# Chua.net
KiCad netlist of a schematic drawn in Altium Designer
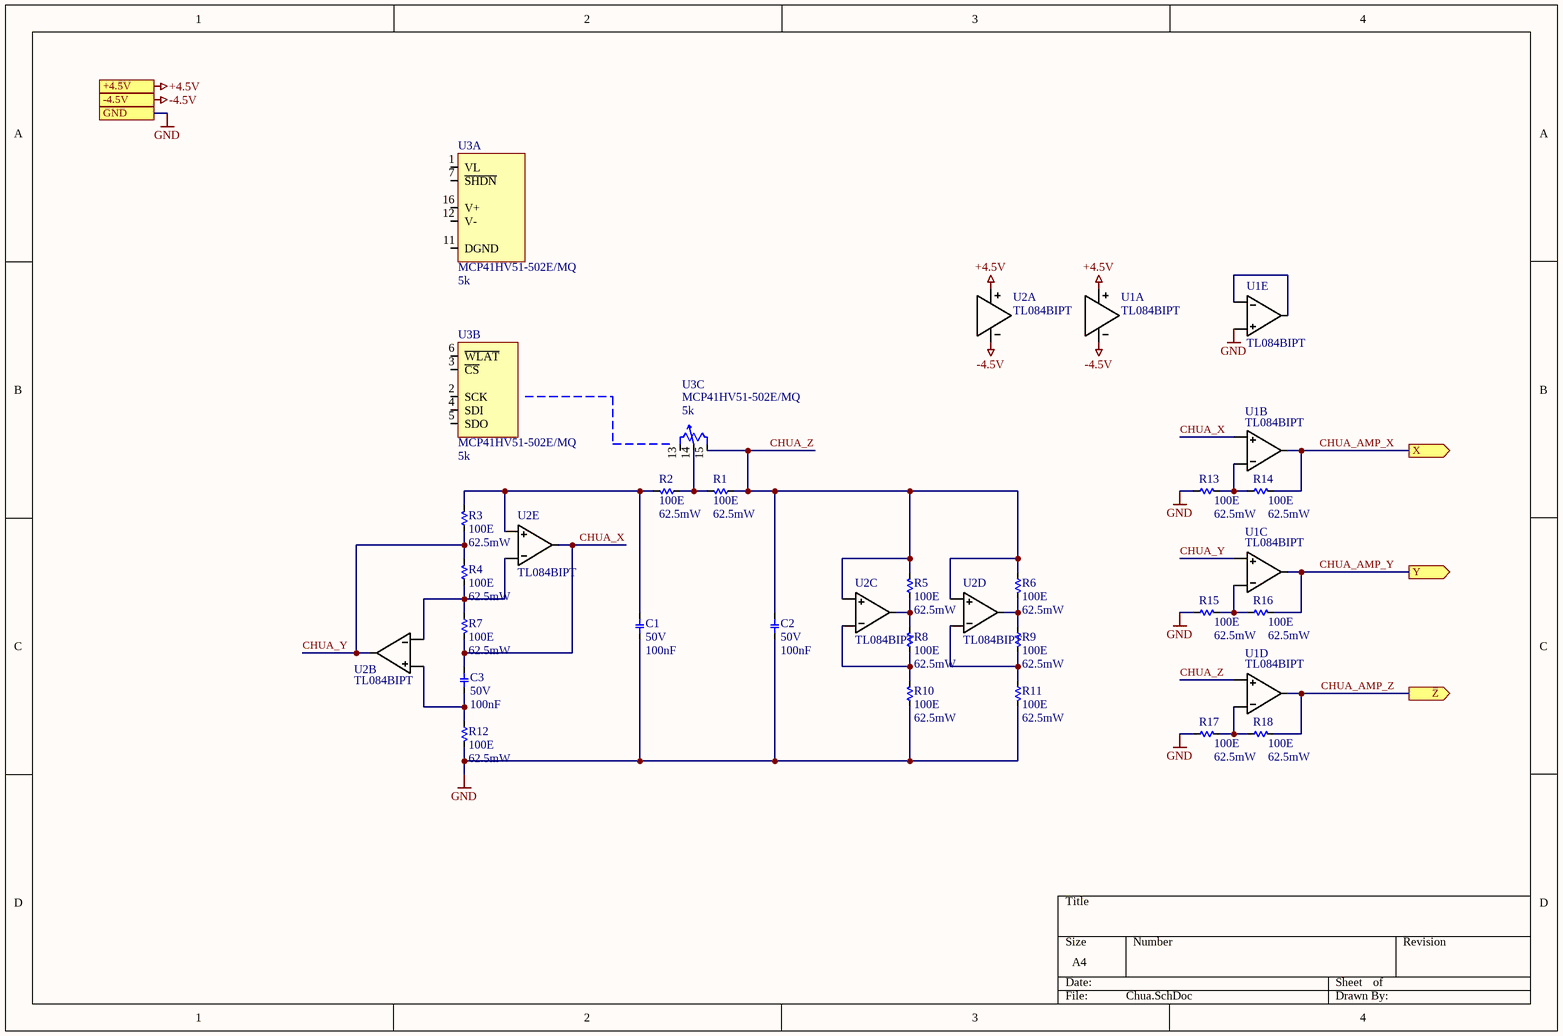
[diagram p0: Chua.SchDoc]

(export (version "E")
  (design (tool "Eeschema 10.0.6"))
  (components
    (comp (ref "C1")
      (value "100nF")
      (footprint "CX7R0402C")
      (description "SMD Capacitor")
      (fields (field (name "VALUE2") "50V") (field (name "Comment") "04025C104JAT2A"))
      (libsource (lib "ChaoticCircuits") (part "kyocera-C-X7R-0402"))
    )
    (comp (ref "C2")
      (value "100nF")
      (footprint "CX7R0402C")
      (description "SMD Capacitor")
      (fields (field (name "VALUE2") "50V") (field (name "Comment") "04025C104JAT2A"))
      (libsource (lib "ChaoticCircuits") (part "kyocera-C-X7R-0402"))
    )
    (comp (ref "C3")
      (value "100nF")
      (footprint "CX7R0402C")
      (description "SMD Capacitor")
      (fields (field (name "VALUE2") "50V") (field (name "Comment") "04025C104JAT2A"))
      (libsource (lib "ChaoticCircuits") (part "kyocera-C-X7R-0402"))
    )
    (comp (ref "R1")
      (value "100E")
      (footprint "RC0402")
      (description "SMD Resistor")
      (fields (field (name "VALUE2") "62.5mW") (field (name "Comment") "0402FR-07100RL"))
      (libsource (lib "ChaoticCircuits") (part "YAGEO-RC-0402"))
    )
    (comp (ref "R2")
      (value "100E")
      (footprint "RC0402")
      (description "SMD Resistor")
      (fields (field (name "VALUE2") "62.5mW") (field (name "Comment") "0402FR-07100RL"))
      (libsource (lib "ChaoticCircuits") (part "YAGEO-RC-0402"))
    )
    (comp (ref "R3")
      (value "100E")
      (footprint "RC0402")
      (description "SMD Resistor")
      (fields (field (name "VALUE2") "62.5mW") (field (name "Comment") "0402FR-07100RL"))
      (libsource (lib "ChaoticCircuits") (part "YAGEO-RC-0402"))
    )
    (comp (ref "R4")
      (value "100E")
      (footprint "RC0402")
      (description "SMD Resistor")
      (fields (field (name "VALUE2") "62.5mW") (field (name "Comment") "0402FR-07100RL"))
      (libsource (lib "ChaoticCircuits") (part "YAGEO-RC-0402"))
    )
    (comp (ref "R5")
      (value "100E")
      (footprint "RC0402")
      (description "SMD Resistor")
      (fields (field (name "VALUE2") "62.5mW") (field (name "Comment") "0402FR-07100RL"))
      (libsource (lib "ChaoticCircuits") (part "YAGEO-RC-0402"))
    )
    (comp (ref "R6")
      (value "100E")
      (footprint "RC0402")
      (description "SMD Resistor")
      (fields (field (name "VALUE2") "62.5mW") (field (name "Comment") "0402FR-07100RL"))
      (libsource (lib "ChaoticCircuits") (part "YAGEO-RC-0402"))
    )
    (comp (ref "R7")
      (value "100E")
      (footprint "RC0402")
      (description "SMD Resistor")
      (fields (field (name "VALUE2") "62.5mW") (field (name "Comment") "0402FR-07100RL"))
      (libsource (lib "ChaoticCircuits") (part "YAGEO-RC-0402"))
    )
    (comp (ref "R8")
      (value "100E")
      (footprint "RC0402")
      (description "SMD Resistor")
      (fields (field (name "VALUE2") "62.5mW") (field (name "Comment") "0402FR-07100RL"))
      (libsource (lib "ChaoticCircuits") (part "YAGEO-RC-0402"))
    )
    (comp (ref "R9")
      (value "100E")
      (footprint "RC0402")
      (description "SMD Resistor")
      (fields (field (name "VALUE2") "62.5mW") (field (name "Comment") "0402FR-07100RL"))
      (libsource (lib "ChaoticCircuits") (part "YAGEO-RC-0402"))
    )
    (comp (ref "R10")
      (value "100E")
      (footprint "RC0402")
      (description "SMD Resistor")
      (fields (field (name "VALUE2") "62.5mW") (field (name "Comment") "0402FR-07100RL"))
      (libsource (lib "ChaoticCircuits") (part "YAGEO-RC-0402"))
    )
    (comp (ref "R11")
      (value "100E")
      (footprint "RC0402")
      (description "SMD Resistor")
      (fields (field (name "VALUE2") "62.5mW") (field (name "Comment") "0402FR-07100RL"))
      (libsource (lib "ChaoticCircuits") (part "YAGEO-RC-0402"))
    )
    (comp (ref "R12")
      (value "100E")
      (footprint "RC0402")
      (description "SMD Resistor")
      (fields (field (name "VALUE2") "62.5mW") (field (name "Comment") "0402FR-07100RL"))
      (libsource (lib "ChaoticCircuits") (part "YAGEO-RC-0402"))
    )
    (comp (ref "R13")
      (value "100E")
      (footprint "RC0402")
      (description "SMD Resistor")
      (fields (field (name "VALUE2") "62.5mW") (field (name "Comment") "0402FR-07100RL"))
      (libsource (lib "ChaoticCircuits") (part "YAGEO-RC-0402"))
    )
    (comp (ref "R14")
      (value "100E")
      (footprint "RC0402")
      (description "SMD Resistor")
      (fields (field (name "VALUE2") "62.5mW") (field (name "Comment") "0402FR-07100RL"))
      (libsource (lib "ChaoticCircuits") (part "YAGEO-RC-0402"))
    )
    (comp (ref "R15")
      (value "100E")
      (footprint "RC0402")
      (description "SMD Resistor")
      (fields (field (name "VALUE2") "62.5mW") (field (name "Comment") "0402FR-07100RL"))
      (libsource (lib "ChaoticCircuits") (part "YAGEO-RC-0402"))
    )
    (comp (ref "R16")
      (value "100E")
      (footprint "RC0402")
      (description "SMD Resistor")
      (fields (field (name "VALUE2") "62.5mW") (field (name "Comment") "0402FR-07100RL"))
      (libsource (lib "ChaoticCircuits") (part "YAGEO-RC-0402"))
    )
    (comp (ref "R17")
      (value "100E")
      (footprint "RC0402")
      (description "SMD Resistor")
      (fields (field (name "VALUE2") "62.5mW") (field (name "Comment") "0402FR-07100RL"))
      (libsource (lib "ChaoticCircuits") (part "YAGEO-RC-0402"))
    )
    (comp (ref "R18")
      (value "100E")
      (footprint "RC0402")
      (description "SMD Resistor")
      (fields (field (name "VALUE2") "62.5mW") (field (name "Comment") "0402FR-07100RL"))
      (libsource (lib "ChaoticCircuits") (part "YAGEO-RC-0402"))
    )
    (comp (ref "U1")
      (value "TL084BIPT")
      (footprint "TSSOP14_0.65_C")
      (description "J-FET Amplifier 4 Circuit - 14-TSSOP")
      (libsource (lib "ChaoticCircuits") (part "TL084"))
    )
    (comp (ref "U2")
      (value "TL084BIPT")
      (footprint "TSSOP14_0.65_C")
      (description "J-FET Amplifier 4 Circuit - 14-TSSOP")
      (libsource (lib "ChaoticCircuits") (part "TL084"))
    )
    (comp (ref "U3")
      (value "MCP41HV51-502E/MQ")
      (footprint "QFN20_0.65_C")
      (description "Digital Potentiometer 5k Ohm 1 Circuit 256 Taps SPI Interface 20-VQFN (5x5)")
      (fields (field (name "ALTIUM_VALUE") "5k"))
      (libsource (lib "ChaoticCircuits") (part "MCP41HV51-502E/MQ"))
    )
  )
  (nets
    (net (code "1") (name "+4.5V") (class "Default")
      (node (ref "U1") (pin "4") (pinfunction "VCC+_4") (pintype "passive"))
      (node (ref "U2") (pin "4") (pinfunction "VCC+_4") (pintype "passive"))
    )
    (net (code "2") (name "-4.5V") (class "Default")
      (node (ref "U1") (pin "11") (pinfunction "VCC-_11") (pintype "passive"))
      (node (ref "U2") (pin "11") (pinfunction "VCC-_11") (pintype "passive"))
    )
    (net (code "3") (name "/CHUA_AMP_X") (class "Default")
      (node (ref "R14") (pin "1") (pinfunction "1_1") (pintype "passive"))
      (node (ref "U1") (pin "1") (pinfunction "OUT1_1") (pintype "passive"))
    )
    (net (code "4") (name "/CHUA_AMP_Y") (class "Default")
      (node (ref "R16") (pin "1") (pinfunction "1_1") (pintype "passive"))
      (node (ref "U1") (pin "7") (pinfunction "OUT2_7") (pintype "passive"))
    )
    (net (code "5") (name "/CHUA_AMP_Z") (class "Default")
      (node (ref "R18") (pin "1") (pinfunction "1_1") (pintype "passive"))
      (node (ref "U1") (pin "8") (pinfunction "OUT3_8") (pintype "passive"))
    )
    (net (code "6") (name "/CHUA_X") (class "Default")
      (node (ref "C3") (pin "2") (pinfunction "2_2") (pintype "passive"))
      (node (ref "R7") (pin "1") (pinfunction "1_1") (pintype "passive"))
      (node (ref "U1") (pin "3") (pinfunction "IN1+_3") (pintype "passive"))
      (node (ref "U2") (pin "14") (pinfunction "OUT4_14") (pintype "passive"))
    )
    (net (code "7") (name "/CHUA_Y") (class "Default")
      (node (ref "R3") (pin "2") (pinfunction "2_2") (pintype "passive"))
      (node (ref "R4") (pin "1") (pinfunction "1_1") (pintype "passive"))
      (node (ref "U1") (pin "5") (pinfunction "IN2+_5") (pintype "passive"))
      (node (ref "U2") (pin "1") (pinfunction "OUT1_1") (pintype "passive"))
    )
    (net (code "8") (name "/CHUA_Z") (class "Default")
      (node (ref "C2") (pin "2") (pinfunction "2_2") (pintype "passive"))
      (node (ref "R1") (pin "1") (pinfunction "1_1") (pintype "passive"))
      (node (ref "R5") (pin "2") (pinfunction "2_2") (pintype "passive"))
      (node (ref "R6") (pin "2") (pinfunction "2_2") (pintype "passive"))
      (node (ref "U1") (pin "10") (pinfunction "IN3+_10") (pintype "passive"))
      (node (ref "U2") (pin "10") (pinfunction "IN3+_10") (pintype "passive"))
      (node (ref "U2") (pin "5") (pinfunction "IN2+_5") (pintype "passive"))
      (node (ref "U3") (pin "15") (pinfunction "P0A_15") (pintype "passive"))
    )
    (net (code "9") (name "GND") (class "Default")
      (node (ref "C1") (pin "1") (pinfunction "1_1") (pintype "passive"))
      (node (ref "C2") (pin "1") (pinfunction "1_1") (pintype "passive"))
      (node (ref "R10") (pin "1") (pinfunction "1_1") (pintype "passive"))
      (node (ref "R11") (pin "1") (pinfunction "1_1") (pintype "passive"))
      (node (ref "R12") (pin "1") (pinfunction "1_1") (pintype "passive"))
      (node (ref "R13") (pin "2") (pinfunction "2_2") (pintype "passive"))
      (node (ref "R15") (pin "2") (pinfunction "2_2") (pintype "passive"))
      (node (ref "R17") (pin "2") (pinfunction "2_2") (pintype "passive"))
      (node (ref "U1") (pin "12") (pinfunction "IN4+_12") (pintype "passive"))
    )
    (net (code "10") (name "Net-(U1B-IN1-)") (class "Default")
      (node (ref "R13") (pin "1") (pinfunction "1_1") (pintype "passive"))
      (node (ref "R14") (pin "2") (pinfunction "2_2") (pintype "passive"))
      (node (ref "U1") (pin "2") (pinfunction "IN1-_2") (pintype "passive"))
    )
    (net (code "11") (name "Net-(U1C-IN2-)") (class "Default")
      (node (ref "R15") (pin "1") (pinfunction "1_1") (pintype "passive"))
      (node (ref "R16") (pin "2") (pinfunction "2_2") (pintype "passive"))
      (node (ref "U1") (pin "6") (pinfunction "IN2-_6") (pintype "passive"))
    )
    (net (code "12") (name "Net-(U1D-IN3-)") (class "Default")
      (node (ref "R17") (pin "1") (pinfunction "1_1") (pintype "passive"))
      (node (ref "R18") (pin "2") (pinfunction "2_2") (pintype "passive"))
      (node (ref "U1") (pin "9") (pinfunction "IN3-_9") (pintype "passive"))
    )
    (net (code "13") (name "Net-(U1E-IN4-)") (class "Default")
      (node (ref "U1") (pin "13") (pinfunction "IN4-_13") (pintype "passive"))
      (node (ref "U1") (pin "14") (pinfunction "OUT4_14") (pintype "passive"))
    )
    (net (code "14") (name "Net-(U2B-IN1+)") (class "Default")
      (node (ref "C3") (pin "1") (pinfunction "1_1") (pintype "passive"))
      (node (ref "R12") (pin "2") (pinfunction "2_2") (pintype "passive"))
      (node (ref "U2") (pin "3") (pinfunction "IN1+_3") (pintype "passive"))
    )
    (net (code "15") (name "Net-(U2B-IN1-)") (class "Default")
      (node (ref "R4") (pin "2") (pinfunction "2_2") (pintype "passive"))
      (node (ref "R7") (pin "2") (pinfunction "2_2") (pintype "passive"))
      (node (ref "U2") (pin "13") (pinfunction "IN4-_13") (pintype "passive"))
      (node (ref "U2") (pin "2") (pinfunction "IN1-_2") (pintype "passive"))
    )
    (net (code "16") (name "Net-(U2C-IN2-)") (class "Default")
      (node (ref "R10") (pin "2") (pinfunction "2_2") (pintype "passive"))
      (node (ref "R8") (pin "1") (pinfunction "1_1") (pintype "passive"))
      (node (ref "U2") (pin "6") (pinfunction "IN2-_6") (pintype "passive"))
    )
    (net (code "17") (name "Net-(U2C-OUT2)") (class "Default")
      (node (ref "R5") (pin "1") (pinfunction "1_1") (pintype "passive"))
      (node (ref "R8") (pin "2") (pinfunction "2_2") (pintype "passive"))
      (node (ref "U2") (pin "7") (pinfunction "OUT2_7") (pintype "passive"))
    )
    (net (code "18") (name "Net-(U2D-IN3-)") (class "Default")
      (node (ref "R11") (pin "2") (pinfunction "2_2") (pintype "passive"))
      (node (ref "R9") (pin "1") (pinfunction "1_1") (pintype "passive"))
      (node (ref "U2") (pin "9") (pinfunction "IN3-_9") (pintype "passive"))
    )
    (net (code "19") (name "Net-(U2D-OUT3)") (class "Default")
      (node (ref "R6") (pin "1") (pinfunction "1_1") (pintype "passive"))
      (node (ref "R9") (pin "2") (pinfunction "2_2") (pintype "passive"))
      (node (ref "U2") (pin "8") (pinfunction "OUT3_8") (pintype "passive"))
    )
    (net (code "20") (name "Net-(U2E-IN4+)") (class "Default")
      (node (ref "C1") (pin "2") (pinfunction "2_2") (pintype "passive"))
      (node (ref "R2") (pin "2") (pinfunction "2_2") (pintype "passive"))
      (node (ref "R3") (pin "1") (pinfunction "1_1") (pintype "passive"))
      (node (ref "U2") (pin "12") (pinfunction "IN4+_12") (pintype "passive"))
    )
    (net (code "21") (name "Net-(U3C-P0W)") (class "Default")
      (node (ref "R1") (pin "2") (pinfunction "2_2") (pintype "passive"))
      (node (ref "R2") (pin "1") (pinfunction "1_1") (pintype "passive"))
      (node (ref "U3") (pin "14") (pinfunction "P0W_14") (pintype "passive"))
    )
    (net (code "22") (name "unconnected-(U3A-DGND-Pad11)") (class "Default")
      (node (ref "U3") (pin "11") (pinfunction "DGND_11") (pintype "passive"))
    )
    (net (code "23") (name "unconnected-(U3A-V+-Pad16)") (class "Default")
      (node (ref "U3") (pin "16") (pinfunction "V+_16") (pintype "passive"))
    )
    (net (code "24") (name "unconnected-(U3A-V--Pad12)") (class "Default")
      (node (ref "U3") (pin "12") (pinfunction "V-_12") (pintype "passive"))
    )
    (net (code "25") (name "unconnected-(U3A-VL-Pad1)") (class "Default")
      (node (ref "U3") (pin "1") (pinfunction "VL_1") (pintype "passive"))
    )
    (net (code "26") (name "unconnected-(U3A-~{SHDN}-Pad7)") (class "Default")
      (node (ref "U3") (pin "7") (pinfunction "~{SHDN}_7") (pintype "passive"))
    )
    (net (code "27") (name "unconnected-(U3B-SCK-Pad2)") (class "Default")
      (node (ref "U3") (pin "2") (pinfunction "SCK_2") (pintype "passive"))
    )
    (net (code "28") (name "unconnected-(U3B-SDI-Pad4)") (class "Default")
      (node (ref "U3") (pin "4") (pinfunction "SDI_4") (pintype "passive"))
    )
    (net (code "29") (name "unconnected-(U3B-SDO-Pad5)") (class "Default")
      (node (ref "U3") (pin "5") (pinfunction "SDO_5") (pintype "passive"))
    )
    (net (code "30") (name "unconnected-(U3B-~{CS}-Pad3)") (class "Default")
      (node (ref "U3") (pin "3") (pinfunction "~{CS}_3") (pintype "passive"))
    )
    (net (code "31") (name "unconnected-(U3B-~{WLAT}-Pad6)") (class "Default")
      (node (ref "U3") (pin "6") (pinfunction "~{WLAT}_6") (pintype "passive"))
    )
    (net (code "32") (name "unconnected-(U3C-P0B-Pad13)") (class "Default")
      (node (ref "U3") (pin "13") (pinfunction "P0B_13") (pintype "passive"))
    )
  )
)
